# Switch.net
KiCad netlist of a schematic drawn in Altium Designer
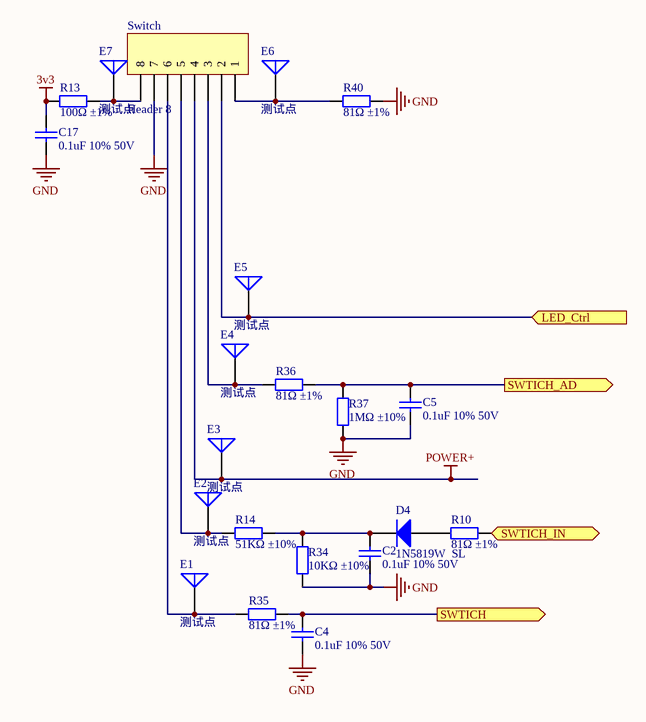
[diagram p0: Switch.SchDoc]

(export (version "E")
  (design (tool "Eeschema 10.0.6"))
  (components
    (comp (ref "C2")
      (value "0.1uF 10% 50V")
      (footprint "0603_C")
      (description "贴片电容")
      (libsource (lib "Cap") (part "0603 4.7uF (475) 10% 16V"))
    )
    (comp (ref "C4")
      (value "0.1uF 10% 50V")
      (footprint "0603_C")
      (description "贴片电容")
      (libsource (lib "Cap") (part "0603 4.7uF (475) 10% 16V"))
    )
    (comp (ref "C5")
      (value "0.1uF 10% 50V")
      (footprint "0603_C")
      (description "贴片电容")
      (libsource (lib "Cap") (part "0603 4.7uF (475) 10% 16V"))
    )
    (comp (ref "C17")
      (value "0.1uF 10% 50V")
      (footprint "0603_C")
      (description "贴片电容")
      (libsource (lib "Cap") (part "0603 4.7uF (475) 10% 16V"))
    )
    (comp (ref "D4")
      (value "1N5819W  SL")
      (footprint "SOD-123")
      (description "肖特基二极管")
      (libsource (lib "Diode") (part "SOD-123 B5819W  SL"))
    )
    (comp (ref "E1")
      (value "测试点")
      (footprint "Test")
      (description "Generic Antenna")
      (fields (field (name "PUBLISHER") "Altium Limited"))
      (libsource (lib "Miscellaneous Devices") (part "Antenna"))
    )
    (comp (ref "E2")
      (value "测试点")
      (footprint "Test")
      (description "Generic Antenna")
      (fields (field (name "PUBLISHER") "Altium Limited"))
      (libsource (lib "Miscellaneous Devices") (part "Antenna"))
    )
    (comp (ref "E3")
      (value "测试点")
      (footprint "Test")
      (description "Generic Antenna")
      (fields (field (name "PUBLISHER") "Altium Limited"))
      (libsource (lib "Miscellaneous Devices") (part "Antenna"))
    )
    (comp (ref "E4")
      (value "测试点")
      (footprint "Test")
      (description "Generic Antenna")
      (fields (field (name "PUBLISHER") "Altium Limited"))
      (libsource (lib "Miscellaneous Devices") (part "Antenna"))
    )
    (comp (ref "E5")
      (value "测试点")
      (footprint "Test")
      (description "Generic Antenna")
      (fields (field (name "PUBLISHER") "Altium Limited"))
      (libsource (lib "Miscellaneous Devices") (part "Antenna"))
    )
    (comp (ref "E6")
      (value "测试点")
      (footprint "Test")
      (description "Generic Antenna")
      (fields (field (name "PUBLISHER") "Altium Limited"))
      (libsource (lib "Miscellaneous Devices") (part "Antenna"))
    )
    (comp (ref "E7")
      (value "测试点")
      (footprint "Test")
      (description "Generic Antenna")
      (fields (field (name "PUBLISHER") "Altium Limited"))
      (libsource (lib "Miscellaneous Devices") (part "Antenna"))
    )
    (comp (ref "R10")
      (value "81Ω ±1%")
      (footprint "0603_R")
      (description "贴片电阻")
      (libsource (lib "") (part "0603 2.2Ω (2R20) 1%_1"))
    )
    (comp (ref "R13")
      (value "100Ω ±1%")
      (footprint "0603_R")
      (description "贴片电阻")
      (libsource (lib "") (part "0603 2.2Ω (2R20) 1%_1"))
    )
    (comp (ref "R14")
      (value "51KΩ ±10%")
      (footprint "0603_R")
      (description "贴片电阻")
      (libsource (lib "") (part "0603 2.2Ω (2R20) 1%_1"))
    )
    (comp (ref "R34")
      (value "10KΩ ±10%")
      (footprint "0603_R")
      (description "贴片电阻")
      (libsource (lib "RES") (part "0603 2.2Ω (2R20) 1%"))
    )
    (comp (ref "R35")
      (value "81Ω ±1%")
      (footprint "0603_R")
      (description "贴片电阻")
      (libsource (lib "") (part "0603 2.2Ω (2R20) 1%_1"))
    )
    (comp (ref "R36")
      (value "81Ω ±1%")
      (footprint "0603_R")
      (description "贴片电阻")
      (libsource (lib "") (part "0603 2.2Ω (2R20) 1%_1"))
    )
    (comp (ref "R37")
      (value "1MΩ ±10%")
      (footprint "0603_R")
      (description "贴片电阻")
      (libsource (lib "RES") (part "0603 2.2Ω (2R20) 1%"))
    )
    (comp (ref "R40")
      (value "81Ω ±1%")
      (footprint "0603_R")
      (description "贴片电阻")
      (libsource (lib "") (part "0603 2.2Ω (2R20) 1%_1"))
    )
    (comp (ref "Switch")
      (value "Header 8")
      (footprint "SH1.0mm-8P")
      (description "Header, 8-Pin")
      (fields (field (name "PUBLISHER") "Altium Limited"))
      (libsource (lib "Miscellaneous Connectors") (part "Header 8"))
    )
  )
  (nets
    (net (code "1") (name "/LED_Ctrl") (class "Default")
      (node (ref "E5") (pin "1") (pinfunction "A_1") (pintype "passive"))
      (node (ref "Switch") (pin "2") (pinfunction "2_2") (pintype "passive"))
    )
    (net (code "2") (name "/SWTICH") (class "Default")
      (node (ref "C4") (pin "2") (pinfunction "2_2") (pintype "passive"))
      (node (ref "R35") (pin "2") (pinfunction "2_2") (pintype "passive"))
    )
    (net (code "3") (name "/SWTICH_AD") (class "Default")
      (node (ref "C5") (pin "2") (pinfunction "2_2") (pintype "passive"))
      (node (ref "R36") (pin "2") (pinfunction "2_2") (pintype "passive"))
      (node (ref "R37") (pin "2") (pinfunction "2_2") (pintype "passive"))
    )
    (net (code "4") (name "/SWTICH_IN") (class "Default")
      (node (ref "R10") (pin "2") (pinfunction "2_2") (pintype "passive"))
    )
    (net (code "5") (name "3v3") (class "Default")
      (node (ref "C17") (pin "2") (pinfunction "2_2") (pintype "passive"))
      (node (ref "R13") (pin "1") (pinfunction "1_1") (pintype "passive"))
    )
    (net (code "6") (name "GND") (class "Default")
      (node (ref "C17") (pin "1") (pinfunction "1_1") (pintype "passive"))
      (node (ref "C2") (pin "1") (pinfunction "1_1") (pintype "passive"))
      (node (ref "C4") (pin "1") (pinfunction "1_1") (pintype "passive"))
      (node (ref "C5") (pin "1") (pinfunction "1_1") (pintype "passive"))
      (node (ref "R34") (pin "1") (pinfunction "1_1") (pintype "passive"))
      (node (ref "R37") (pin "1") (pinfunction "1_1") (pintype "passive"))
      (node (ref "R40") (pin "2") (pinfunction "2_2") (pintype "passive"))
      (node (ref "Switch") (pin "7") (pinfunction "7_7") (pintype "passive"))
    )
    (net (code "7") (name "Net-(D4-A)") (class "Default")
      (node (ref "D4") (pin "1") (pinfunction "A_1") (pintype "passive"))
      (node (ref "R10") (pin "1") (pinfunction "1_1") (pintype "passive"))
    )
    (net (code "8") (name "Net-(D4-K)") (class "Default")
      (node (ref "C2") (pin "2") (pinfunction "2_2") (pintype "passive"))
      (node (ref "D4") (pin "2") (pinfunction "K_2") (pintype "passive"))
      (node (ref "R14") (pin "2") (pinfunction "2_2") (pintype "passive"))
      (node (ref "R34") (pin "2") (pinfunction "2_2") (pintype "passive"))
    )
    (net (code "9") (name "Net-(E1-A)") (class "Default")
      (node (ref "E1") (pin "1") (pinfunction "A_1") (pintype "passive"))
      (node (ref "R35") (pin "1") (pinfunction "1_1") (pintype "passive"))
      (node (ref "Switch") (pin "6") (pinfunction "6_6") (pintype "passive"))
    )
    (net (code "10") (name "Net-(E2-A)") (class "Default")
      (node (ref "E2") (pin "1") (pinfunction "A_1") (pintype "passive"))
      (node (ref "R14") (pin "1") (pinfunction "1_1") (pintype "passive"))
      (node (ref "Switch") (pin "5") (pinfunction "5_5") (pintype "passive"))
    )
    (net (code "11") (name "Net-(E4-A)") (class "Default")
      (node (ref "E4") (pin "1") (pinfunction "A_1") (pintype "passive"))
      (node (ref "R36") (pin "1") (pinfunction "1_1") (pintype "passive"))
      (node (ref "Switch") (pin "3") (pinfunction "3_3") (pintype "passive"))
    )
    (net (code "12") (name "Net-(E6-A)") (class "Default")
      (node (ref "E6") (pin "1") (pinfunction "A_1") (pintype "passive"))
      (node (ref "R40") (pin "1") (pinfunction "1_1") (pintype "passive"))
      (node (ref "Switch") (pin "1") (pinfunction "1_1") (pintype "passive"))
    )
    (net (code "13") (name "Net-(E7-A)") (class "Default")
      (node (ref "E7") (pin "1") (pinfunction "A_1") (pintype "passive"))
      (node (ref "R13") (pin "2") (pinfunction "2_2") (pintype "passive"))
      (node (ref "Switch") (pin "8") (pinfunction "8_8") (pintype "passive"))
    )
    (net (code "14") (name "POWER+") (class "Default")
      (node (ref "E3") (pin "1") (pinfunction "A_1") (pintype "passive"))
      (node (ref "Switch") (pin "4") (pinfunction "4_4") (pintype "passive"))
    )
  )
)
